# 03-LP_Filter.net
KiCad netlist of a schematic drawn in Altium Designer
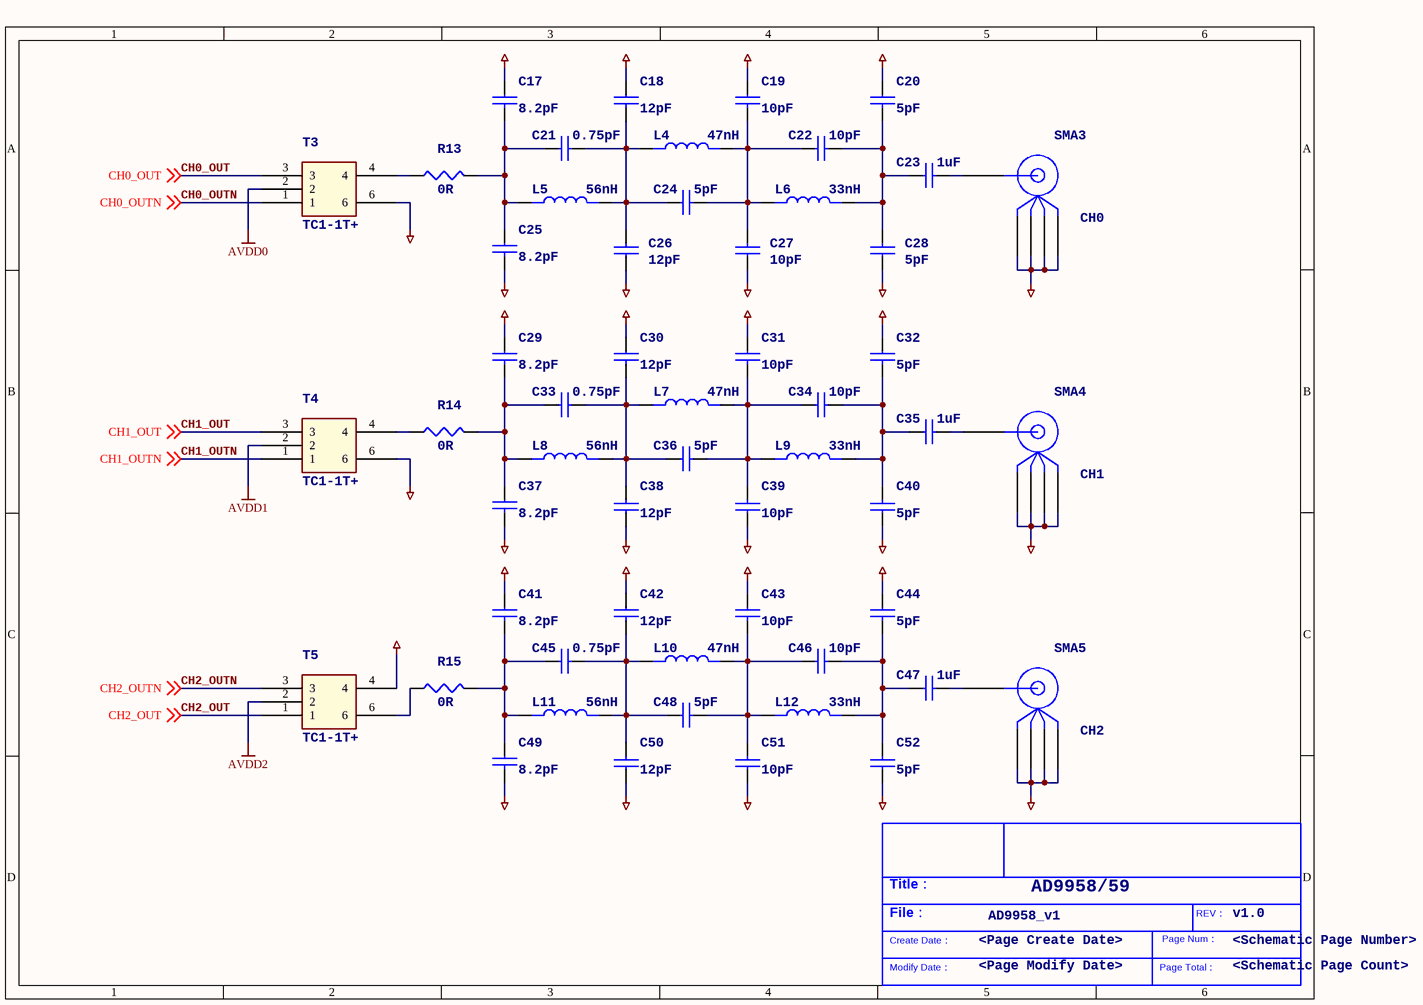
[diagram p0: 03-LP Filter.SchDoc]

(export (version "E")
  (design (tool "Eeschema 10.0.6"))
  (components
    (comp (ref "C17") (value "8.2pF") (footprint "0603C") (libsource (lib "*") (part "CAP NP")))
    (comp (ref "C18") (value "12pF") (footprint "0603C") (libsource (lib "*") (part "CAP NP")))
    (comp (ref "C19") (value "10pF") (footprint "0603C") (libsource (lib "*") (part "CAP NP")))
    (comp (ref "C20") (value "5pF") (footprint "0603C") (libsource (lib "*") (part "CAP NP")))
    (comp (ref "C21") (value "0.75pF") (footprint "0603C") (libsource (lib "*") (part "CAP NP")))
    (comp (ref "C22") (value "10pF") (footprint "0603C") (libsource (lib "*") (part "CAP NP")))
    (comp (ref "C23") (value "1uF") (footprint "0603C") (libsource (lib "*") (part "CAP NP")))
    (comp (ref "C24") (value "5pF") (footprint "0603C") (libsource (lib "*") (part "CAP NP")))
    (comp (ref "C25") (value "8.2pF") (footprint "0603C") (libsource (lib "*") (part "CAP NP")))
    (comp (ref "C26") (value "12pF") (footprint "0603C") (libsource (lib "*") (part "CAP NP")))
    (comp (ref "C27") (value "10pF") (footprint "0603C") (libsource (lib "*") (part "CAP NP")))
    (comp (ref "C28") (value "5pF") (footprint "0603C") (libsource (lib "*") (part "CAP NP")))
    (comp (ref "C29") (value "8.2pF") (footprint "0603C") (libsource (lib "*") (part "CAP NP")))
    (comp (ref "C30") (value "12pF") (footprint "0603C") (libsource (lib "*") (part "CAP NP")))
    (comp (ref "C31") (value "10pF") (footprint "0603C") (libsource (lib "*") (part "CAP NP")))
    (comp (ref "C32") (value "5pF") (footprint "0603C") (libsource (lib "*") (part "CAP NP")))
    (comp (ref "C33") (value "0.75pF") (footprint "0603C") (libsource (lib "*") (part "CAP NP")))
    (comp (ref "C34") (value "10pF") (footprint "0603C") (libsource (lib "*") (part "CAP NP")))
    (comp (ref "C35") (value "1uF") (footprint "0603C") (libsource (lib "*") (part "CAP NP")))
    (comp (ref "C36") (value "5pF") (footprint "0603C") (libsource (lib "*") (part "CAP NP")))
    (comp (ref "C37") (value "8.2pF") (footprint "0603C") (libsource (lib "*") (part "CAP NP")))
    (comp (ref "C38") (value "12pF") (footprint "0603C") (libsource (lib "*") (part "CAP NP")))
    (comp (ref "C39") (value "10pF") (footprint "0603C") (libsource (lib "*") (part "CAP NP")))
    (comp (ref "C40") (value "5pF") (footprint "0603C") (libsource (lib "*") (part "CAP NP")))
    (comp (ref "C41") (value "8.2pF") (footprint "0603C") (libsource (lib "*") (part "CAP NP")))
    (comp (ref "C42") (value "12pF") (footprint "0603C") (libsource (lib "*") (part "CAP NP")))
    (comp (ref "C43") (value "10pF") (footprint "0603C") (libsource (lib "*") (part "CAP NP")))
    (comp (ref "C44") (value "5pF") (footprint "0603C") (libsource (lib "*") (part "CAP NP")))
    (comp (ref "C45") (value "0.75pF") (footprint "0603C") (libsource (lib "*") (part "CAP NP")))
    (comp (ref "C46") (value "10pF") (footprint "0603C") (libsource (lib "*") (part "CAP NP")))
    (comp (ref "C47") (value "1uF") (footprint "0603C") (libsource (lib "*") (part "CAP NP")))
    (comp (ref "C48") (value "5pF") (footprint "0603C") (libsource (lib "*") (part "CAP NP")))
    (comp (ref "C49") (value "8.2pF") (footprint "0603C") (libsource (lib "*") (part "CAP NP")))
    (comp (ref "C50") (value "12pF") (footprint "0603C") (libsource (lib "*") (part "CAP NP")))
    (comp (ref "C51") (value "10pF") (footprint "0603C") (libsource (lib "*") (part "CAP NP")))
    (comp (ref "C52") (value "5pF") (footprint "0603C") (libsource (lib "*") (part "CAP NP")))
    (comp (ref "L4") (value "47nH") (footprint "0603L") (libsource (lib "*") (part "INDUCTANCE")))
    (comp (ref "L5") (value "56nH") (footprint "0603L") (libsource (lib "*") (part "INDUCTANCE")))
    (comp (ref "L6") (value "33nH") (footprint "0603L") (libsource (lib "*") (part "INDUCTANCE")))
    (comp (ref "L7") (value "47nH") (footprint "0603L") (libsource (lib "*") (part "INDUCTANCE")))
    (comp (ref "L8") (value "56nH") (footprint "0603L") (libsource (lib "*") (part "INDUCTANCE")))
    (comp (ref "L9") (value "33nH") (footprint "0603L") (libsource (lib "*") (part "INDUCTANCE")))
    (comp (ref "L10") (value "47nH") (footprint "0603L") (libsource (lib "*") (part "INDUCTANCE")))
    (comp (ref "L11") (value "56nH") (footprint "0603L") (libsource (lib "*") (part "INDUCTANCE")))
    (comp (ref "L12") (value "33nH") (footprint "0603L") (libsource (lib "*") (part "INDUCTANCE")))
    (comp (ref "R13") (value "0R") (footprint "0603R") (libsource (lib "*") (part "R")))
    (comp (ref "R14") (value "0R") (footprint "0603R") (libsource (lib "*") (part "R")))
    (comp (ref "R15") (value "0R") (footprint "0603R") (libsource (lib "*") (part "R")))
    (comp (ref "SMA3") (value "CH0") (footprint "SMA-SMD") (libsource (lib "*") (part "BNC")))
    (comp (ref "SMA4") (value "CH1") (footprint "SMA-SMD") (libsource (lib "*") (part "BNC")))
    (comp (ref "SMA5") (value "CH2") (footprint "SMA-SMD") (libsource (lib "*") (part "BNC")))
    (comp (ref "T3") (value "TC1-1T+") (libsource (lib "*") (part "TC1-1T+")))
    (comp (ref "T4") (value "TC1-1T+") (libsource (lib "*") (part "TC1-1T+")))
    (comp (ref "T5") (value "TC1-1T+") (libsource (lib "*") (part "TC1-1T+")))
  )
  (nets
    (net (code "1") (name "AGND") (class "Default")
      (node (ref "C17") (pin "1") (pinfunction "1_1") (pintype "passive"))
      (node (ref "C18") (pin "1") (pinfunction "1_1") (pintype "passive"))
      (node (ref "C19") (pin "1") (pinfunction "1_1") (pintype "passive"))
      (node (ref "C20") (pin "1") (pinfunction "1_1") (pintype "passive"))
      (node (ref "C25") (pin "2") (pinfunction "2_2") (pintype "passive"))
      (node (ref "C26") (pin "1") (pinfunction "1_1") (pintype "passive"))
      (node (ref "C27") (pin "1") (pinfunction "1_1") (pintype "passive"))
      (node (ref "C28") (pin "1") (pinfunction "1_1") (pintype "passive"))
      (node (ref "C29") (pin "1") (pinfunction "1_1") (pintype "passive"))
      (node (ref "C30") (pin "1") (pinfunction "1_1") (pintype "passive"))
      (node (ref "C31") (pin "1") (pinfunction "1_1") (pintype "passive"))
      (node (ref "C32") (pin "1") (pinfunction "1_1") (pintype "passive"))
      (node (ref "C37") (pin "2") (pinfunction "2_2") (pintype "passive"))
      (node (ref "C38") (pin "1") (pinfunction "1_1") (pintype "passive"))
      (node (ref "C39") (pin "1") (pinfunction "1_1") (pintype "passive"))
      (node (ref "C40") (pin "1") (pinfunction "1_1") (pintype "passive"))
      (node (ref "C41") (pin "1") (pinfunction "1_1") (pintype "passive"))
      (node (ref "C42") (pin "1") (pinfunction "1_1") (pintype "passive"))
      (node (ref "C43") (pin "1") (pinfunction "1_1") (pintype "passive"))
      (node (ref "C44") (pin "1") (pinfunction "1_1") (pintype "passive"))
      (node (ref "C49") (pin "2") (pinfunction "2_2") (pintype "passive"))
      (node (ref "C50") (pin "1") (pinfunction "1_1") (pintype "passive"))
      (node (ref "C51") (pin "1") (pinfunction "1_1") (pintype "passive"))
      (node (ref "C52") (pin "1") (pinfunction "1_1") (pintype "passive"))
      (node (ref "SMA3") (pin "2") (pinfunction "GND_2") (pintype "power_in"))
      (node (ref "SMA3") (pin "3") (pinfunction "GND_3") (pintype "power_in"))
      (node (ref "SMA3") (pin "4") (pinfunction "GND_4") (pintype "power_in"))
      (node (ref "SMA3") (pin "5") (pinfunction "GND_5") (pintype "power_in"))
      (node (ref "SMA4") (pin "2") (pinfunction "GND_2") (pintype "power_in"))
      (node (ref "SMA4") (pin "3") (pinfunction "GND_3") (pintype "power_in"))
      (node (ref "SMA4") (pin "4") (pinfunction "GND_4") (pintype "power_in"))
      (node (ref "SMA4") (pin "5") (pinfunction "GND_5") (pintype "power_in"))
      (node (ref "SMA5") (pin "2") (pinfunction "GND_2") (pintype "power_in"))
      (node (ref "SMA5") (pin "3") (pinfunction "GND_3") (pintype "power_in"))
      (node (ref "SMA5") (pin "4") (pinfunction "GND_4") (pintype "power_in"))
      (node (ref "SMA5") (pin "5") (pinfunction "GND_5") (pintype "power_in"))
      (node (ref "T3") (pin "6") (pinfunction "6_6") (pintype "passive"))
      (node (ref "T4") (pin "6") (pinfunction "6_6") (pintype "passive"))
      (node (ref "T5") (pin "4") (pinfunction "4_4") (pintype "passive"))
    )
    (net (code "2") (name "AVDD0") (class "Default")
      (node (ref "T3") (pin "2") (pinfunction "2_2") (pintype "passive"))
    )
    (net (code "3") (name "AVDD1") (class "Default")
      (node (ref "T4") (pin "2") (pinfunction "2_2") (pintype "passive"))
    )
    (net (code "4") (name "AVDD2") (class "Default")
      (node (ref "T5") (pin "2") (pinfunction "2_2") (pintype "passive"))
    )
    (net (code "5") (name "CH0_OUT") (class "Default")
      (node (ref "T3") (pin "3") (pinfunction "3_3") (pintype "passive"))
    )
    (net (code "6") (name "CH0_OUTN") (class "Default")
      (node (ref "T3") (pin "1") (pinfunction "1_1") (pintype "passive"))
    )
    (net (code "7") (name "CH1_OUT") (class "Default")
      (node (ref "T4") (pin "3") (pinfunction "3_3") (pintype "passive"))
    )
    (net (code "8") (name "CH1_OUTN") (class "Default")
      (node (ref "T4") (pin "1") (pinfunction "1_1") (pintype "passive"))
    )
    (net (code "9") (name "CH2_OUT") (class "Default")
      (node (ref "T5") (pin "1") (pinfunction "1_1") (pintype "passive"))
    )
    (net (code "10") (name "CH2_OUTN") (class "Default")
      (node (ref "T5") (pin "3") (pinfunction "3_3") (pintype "passive"))
    )
    (net (code "11") (name "Net-(C17-Pad2)") (class "Default")
      (node (ref "C17") (pin "2") (pinfunction "2_2") (pintype "passive"))
      (node (ref "C21") (pin "1") (pinfunction "1_1") (pintype "passive"))
      (node (ref "C25") (pin "1") (pinfunction "1_1") (pintype "passive"))
      (node (ref "L5") (pin "1") (pinfunction "1_1") (pintype "passive"))
      (node (ref "R13") (pin "2") (pinfunction "2_2") (pintype "passive"))
    )
    (net (code "12") (name "Net-(C18-Pad2)") (class "Default")
      (node (ref "C18") (pin "2") (pinfunction "2_2") (pintype "passive"))
      (node (ref "C21") (pin "2") (pinfunction "2_2") (pintype "passive"))
      (node (ref "C24") (pin "1") (pinfunction "1_1") (pintype "passive"))
      (node (ref "C26") (pin "2") (pinfunction "2_2") (pintype "passive"))
      (node (ref "L4") (pin "1") (pinfunction "1_1") (pintype "passive"))
      (node (ref "L5") (pin "2") (pinfunction "2_2") (pintype "passive"))
    )
    (net (code "13") (name "Net-(C19-Pad2)") (class "Default")
      (node (ref "C19") (pin "2") (pinfunction "2_2") (pintype "passive"))
      (node (ref "C22") (pin "1") (pinfunction "1_1") (pintype "passive"))
      (node (ref "C24") (pin "2") (pinfunction "2_2") (pintype "passive"))
      (node (ref "C27") (pin "2") (pinfunction "2_2") (pintype "passive"))
      (node (ref "L4") (pin "2") (pinfunction "2_2") (pintype "passive"))
      (node (ref "L6") (pin "1") (pinfunction "1_1") (pintype "passive"))
    )
    (net (code "14") (name "Net-(C20-Pad2)") (class "Default")
      (node (ref "C20") (pin "2") (pinfunction "2_2") (pintype "passive"))
      (node (ref "C22") (pin "2") (pinfunction "2_2") (pintype "passive"))
      (node (ref "C23") (pin "1") (pinfunction "1_1") (pintype "passive"))
      (node (ref "C28") (pin "2") (pinfunction "2_2") (pintype "passive"))
      (node (ref "L6") (pin "2") (pinfunction "2_2") (pintype "passive"))
    )
    (net (code "15") (name "Net-(C23-Pad2)") (class "Default")
      (node (ref "C23") (pin "2") (pinfunction "2_2") (pintype "passive"))
      (node (ref "SMA3") (pin "1") (pinfunction "1_1") (pintype "passive"))
    )
    (net (code "16") (name "Net-(C29-Pad2)") (class "Default")
      (node (ref "C29") (pin "2") (pinfunction "2_2") (pintype "passive"))
      (node (ref "C33") (pin "1") (pinfunction "1_1") (pintype "passive"))
      (node (ref "C37") (pin "1") (pinfunction "1_1") (pintype "passive"))
      (node (ref "L8") (pin "1") (pinfunction "1_1") (pintype "passive"))
      (node (ref "R14") (pin "2") (pinfunction "2_2") (pintype "passive"))
    )
    (net (code "17") (name "Net-(C30-Pad2)") (class "Default")
      (node (ref "C30") (pin "2") (pinfunction "2_2") (pintype "passive"))
      (node (ref "C33") (pin "2") (pinfunction "2_2") (pintype "passive"))
      (node (ref "C36") (pin "1") (pinfunction "1_1") (pintype "passive"))
      (node (ref "C38") (pin "2") (pinfunction "2_2") (pintype "passive"))
      (node (ref "L7") (pin "1") (pinfunction "1_1") (pintype "passive"))
      (node (ref "L8") (pin "2") (pinfunction "2_2") (pintype "passive"))
    )
    (net (code "18") (name "Net-(C31-Pad2)") (class "Default")
      (node (ref "C31") (pin "2") (pinfunction "2_2") (pintype "passive"))
      (node (ref "C34") (pin "1") (pinfunction "1_1") (pintype "passive"))
      (node (ref "C36") (pin "2") (pinfunction "2_2") (pintype "passive"))
      (node (ref "C39") (pin "2") (pinfunction "2_2") (pintype "passive"))
      (node (ref "L7") (pin "2") (pinfunction "2_2") (pintype "passive"))
      (node (ref "L9") (pin "1") (pinfunction "1_1") (pintype "passive"))
    )
    (net (code "19") (name "Net-(C32-Pad2)") (class "Default")
      (node (ref "C32") (pin "2") (pinfunction "2_2") (pintype "passive"))
      (node (ref "C34") (pin "2") (pinfunction "2_2") (pintype "passive"))
      (node (ref "C35") (pin "1") (pinfunction "1_1") (pintype "passive"))
      (node (ref "C40") (pin "2") (pinfunction "2_2") (pintype "passive"))
      (node (ref "L9") (pin "2") (pinfunction "2_2") (pintype "passive"))
    )
    (net (code "20") (name "Net-(C35-Pad2)") (class "Default")
      (node (ref "C35") (pin "2") (pinfunction "2_2") (pintype "passive"))
      (node (ref "SMA4") (pin "1") (pinfunction "1_1") (pintype "passive"))
    )
    (net (code "21") (name "Net-(C41-Pad2)") (class "Default")
      (node (ref "C41") (pin "2") (pinfunction "2_2") (pintype "passive"))
      (node (ref "C45") (pin "1") (pinfunction "1_1") (pintype "passive"))
      (node (ref "C49") (pin "1") (pinfunction "1_1") (pintype "passive"))
      (node (ref "L11") (pin "1") (pinfunction "1_1") (pintype "passive"))
      (node (ref "R15") (pin "2") (pinfunction "2_2") (pintype "passive"))
    )
    (net (code "22") (name "Net-(C42-Pad2)") (class "Default")
      (node (ref "C42") (pin "2") (pinfunction "2_2") (pintype "passive"))
      (node (ref "C45") (pin "2") (pinfunction "2_2") (pintype "passive"))
      (node (ref "C48") (pin "1") (pinfunction "1_1") (pintype "passive"))
      (node (ref "C50") (pin "2") (pinfunction "2_2") (pintype "passive"))
      (node (ref "L10") (pin "1") (pinfunction "1_1") (pintype "passive"))
      (node (ref "L11") (pin "2") (pinfunction "2_2") (pintype "passive"))
    )
    (net (code "23") (name "Net-(C43-Pad2)") (class "Default")
      (node (ref "C43") (pin "2") (pinfunction "2_2") (pintype "passive"))
      (node (ref "C46") (pin "1") (pinfunction "1_1") (pintype "passive"))
      (node (ref "C48") (pin "2") (pinfunction "2_2") (pintype "passive"))
      (node (ref "C51") (pin "2") (pinfunction "2_2") (pintype "passive"))
      (node (ref "L10") (pin "2") (pinfunction "2_2") (pintype "passive"))
      (node (ref "L12") (pin "1") (pinfunction "1_1") (pintype "passive"))
    )
    (net (code "24") (name "Net-(C44-Pad2)") (class "Default")
      (node (ref "C44") (pin "2") (pinfunction "2_2") (pintype "passive"))
      (node (ref "C46") (pin "2") (pinfunction "2_2") (pintype "passive"))
      (node (ref "C47") (pin "1") (pinfunction "1_1") (pintype "passive"))
      (node (ref "C52") (pin "2") (pinfunction "2_2") (pintype "passive"))
      (node (ref "L12") (pin "2") (pinfunction "2_2") (pintype "passive"))
    )
    (net (code "25") (name "Net-(C47-Pad2)") (class "Default")
      (node (ref "C47") (pin "2") (pinfunction "2_2") (pintype "passive"))
      (node (ref "SMA5") (pin "1") (pinfunction "1_1") (pintype "passive"))
    )
    (net (code "26") (name "Net-(R13-Pad1)") (class "Default")
      (node (ref "R13") (pin "1") (pinfunction "1_1") (pintype "passive"))
      (node (ref "T3") (pin "4") (pinfunction "4_4") (pintype "passive"))
    )
    (net (code "27") (name "Net-(R14-Pad1)") (class "Default")
      (node (ref "R14") (pin "1") (pinfunction "1_1") (pintype "passive"))
      (node (ref "T4") (pin "4") (pinfunction "4_4") (pintype "passive"))
    )
    (net (code "28") (name "Net-(R15-Pad1)") (class "Default")
      (node (ref "R15") (pin "1") (pinfunction "1_1") (pintype "passive"))
      (node (ref "T5") (pin "6") (pinfunction "6_6") (pintype "passive"))
    )
  )
)
